# levelshift6x.net
KiCad netlist of a schematic drawn in Altium Designer
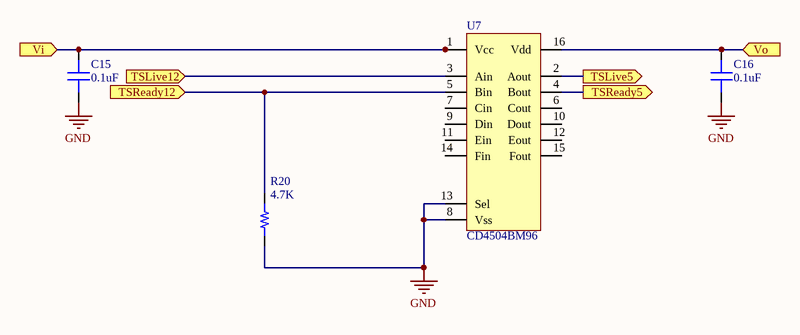
[diagram p0: levelshift6x.SchDoc]

(export (version "E")
  (design (tool "Eeschema 10.0.6"))
  (components
    (comp (ref "C15")
      (value "capacitor")
      (footprint "0603")
      (description "Generic 0603 capacitor")
      (fields (field (name "CAPACITANCE") "0.1uF") (field (name "VOLTAGE") "50"))
      (libsource (lib "altlib") (part "capacitor"))
    )
    (comp (ref "C16")
      (value "capacitor")
      (footprint "0603")
      (description "Generic 0603 capacitor")
      (fields (field (name "CAPACITANCE") "0.1uF") (field (name "VOLTAGE") "50"))
      (libsource (lib "altlib") (part "capacitor"))
    )
    (comp (ref "R20")
      (value "4.7K")
      (footprint "RES 0603/1608")
      (fields (field (name "RESISTANCE") "4.7K"))
      (libsource (lib "altlib") (part "Resistor"))
    )
    (comp (ref "U7")
      (value "CD4504BM96")
      (footprint "SOIC-16")
      (description "Voltage Level Translator Unidirectional 1 Cir")
      (libsource (lib "altlib") (part "CD4504BM96"))
    )
  )
  (nets
    (net (code "1") (name "/TSLive5") (class "Default")
      (node (ref "U7") (pin "2") (pinfunction "Aout_2") (pintype "passive"))
    )
    (net (code "2") (name "/TSLive12") (class "Default")
      (node (ref "U7") (pin "3") (pinfunction "Ain_3") (pintype "passive"))
    )
    (net (code "3") (name "/TSReady5") (class "Default")
      (node (ref "U7") (pin "4") (pinfunction "Bout_4") (pintype "passive"))
    )
    (net (code "4") (name "/TSReady12") (class "Default")
      (node (ref "R20") (pin "2") (pinfunction "2_2") (pintype "passive"))
      (node (ref "U7") (pin "5") (pinfunction "Bin_5") (pintype "passive"))
    )
    (net (code "5") (name "/Vi") (class "Default")
      (node (ref "C15") (pin "2") (pinfunction "2_2") (pintype "passive"))
      (node (ref "U7") (pin "1") (pinfunction "Vcc_1") (pintype "passive"))
    )
    (net (code "6") (name "/Vo") (class "Default")
      (node (ref "C16") (pin "2") (pinfunction "2_2") (pintype "passive"))
      (node (ref "U7") (pin "16") (pinfunction "Vdd_16") (pintype "passive"))
    )
    (net (code "7") (name "GND") (class "Default")
      (node (ref "C15") (pin "1") (pinfunction "1_1") (pintype "passive"))
      (node (ref "C16") (pin "1") (pinfunction "1_1") (pintype "passive"))
      (node (ref "R20") (pin "1") (pinfunction "1_1") (pintype "passive"))
      (node (ref "U7") (pin "13") (pinfunction "Sel_13") (pintype "passive"))
      (node (ref "U7") (pin "8") (pinfunction "Vss_8") (pintype "passive"))
    )
    (net (code "8") (name "unconnected-(U7-Cin-Pad7)") (class "Default")
      (node (ref "U7") (pin "7") (pinfunction "Cin_7") (pintype "passive"))
    )
    (net (code "9") (name "unconnected-(U7-Cout-Pad6)") (class "Default")
      (node (ref "U7") (pin "6") (pinfunction "Cout_6") (pintype "passive"))
    )
    (net (code "10") (name "unconnected-(U7-Din-Pad9)") (class "Default")
      (node (ref "U7") (pin "9") (pinfunction "Din_9") (pintype "passive"))
    )
    (net (code "11") (name "unconnected-(U7-Dout-Pad10)") (class "Default")
      (node (ref "U7") (pin "10") (pinfunction "Dout_10") (pintype "passive"))
    )
    (net (code "12") (name "unconnected-(U7-Ein-Pad11)") (class "Default")
      (node (ref "U7") (pin "11") (pinfunction "Ein_11") (pintype "passive"))
    )
    (net (code "13") (name "unconnected-(U7-Eout-Pad12)") (class "Default")
      (node (ref "U7") (pin "12") (pinfunction "Eout_12") (pintype "passive"))
    )
    (net (code "14") (name "unconnected-(U7-Fin-Pad14)") (class "Default")
      (node (ref "U7") (pin "14") (pinfunction "Fin_14") (pintype "passive"))
    )
    (net (code "15") (name "unconnected-(U7-Fout-Pad15)") (class "Default")
      (node (ref "U7") (pin "15") (pinfunction "Fout_15") (pintype "passive"))
    )
  )
)
